# SIM_Socket.net
KiCad netlist of a schematic drawn in Altium Designer
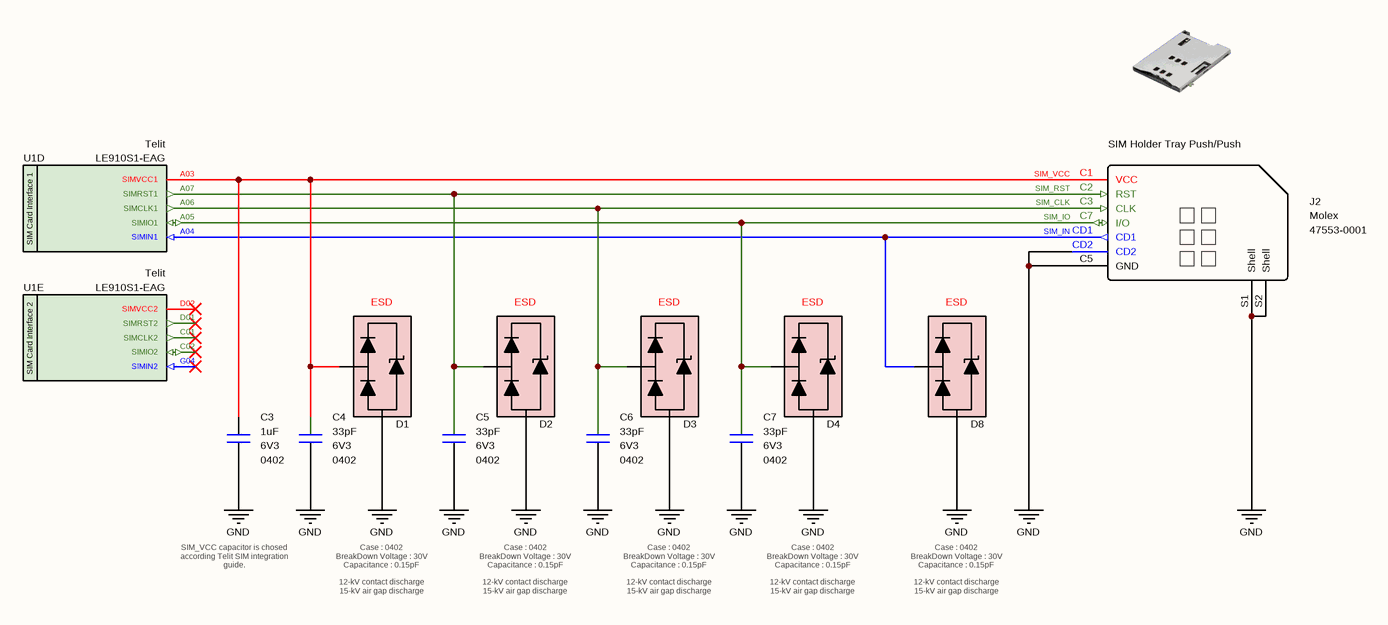
[diagram p0: SIM Socket.SchDoc]

(export (version "E")
  (design (tool "Eeschema 10.0.6"))
  (components
    (comp (ref "C3")
      (value "1uF")
      (footprint "Capacitor 0402")
      (description "Multilayer Ceramic Capacitors - SMD - 6.3V 1uF X5R 0402 20%")
      (fields
        (field (name "MANUFACTURER PART NUMBER") "GRM153R60J105ME95D")
        (field (name "TOLERANCE") "20%")
        (field (name "CASE") "0402")
        (field (name "VOLTAGE") "6V3")
      )
      (libsource (lib "P101DA_Library") (part "1uF [0402-6V3]"))
    )
    (comp (ref "C4")
      (value "33pF")
      (footprint "CAPACITOR_0402")
      (description "Capacitor - 33pF [0402] (Ceramic)")
      (fields
        (field (name "CASE") "0402")
        (field (name "VOLTAGE") "6V3")
        (field (name "MANUFACTURER PART NUMBER") "C0402C330J9RACAUTO")
        (field (name "TOLERANCE") "10%")
      )
      (libsource (lib "P101DA_Library") (part "33pF [0402-6V3]"))
    )
    (comp (ref "C5")
      (value "33pF")
      (footprint "CAPACITOR_0402")
      (description "Capacitor - 33pF [0402] (Ceramic)")
      (fields
        (field (name "CASE") "0402")
        (field (name "VOLTAGE") "6V3")
        (field (name "MANUFACTURER PART NUMBER") "C0402C330J9RACAUTO")
        (field (name "TOLERANCE") "10%")
      )
      (libsource (lib "P101DA_Library") (part "33pF [0402-6V3]"))
    )
    (comp (ref "C6")
      (value "33pF")
      (footprint "CAPACITOR_0402")
      (description "Capacitor - 33pF [0402] (Ceramic)")
      (fields
        (field (name "CASE") "0402")
        (field (name "VOLTAGE") "6V3")
        (field (name "MANUFACTURER PART NUMBER") "C0402C330J9RACAUTO")
        (field (name "TOLERANCE") "10%")
      )
      (libsource (lib "P101DA_Library") (part "33pF [0402-6V3]"))
    )
    (comp (ref "C7")
      (value "33pF")
      (footprint "CAPACITOR_0402")
      (description "Capacitor - 33pF [0402] (Ceramic)")
      (fields
        (field (name "CASE") "0402")
        (field (name "VOLTAGE") "6V3")
        (field (name "MANUFACTURER PART NUMBER") "C0402C330J9RACAUTO")
        (field (name "TOLERANCE") "10%")
      )
      (libsource (lib "P101DA_Library") (part "33pF [0402-6V3]"))
    )
    (comp (ref "D1")
      (value "0402ESDA-MLP1")
      (footprint "ESD_0402")
      (description "SUPPRESSOR ESD 30VDC 0402 HFREE")
      (libsource (lib "P101DA_Library") (part "Diode - TPD1E05U06DPYR"))
    )
    (comp (ref "D2")
      (value "0402ESDA-MLP1")
      (footprint "ESD_0402")
      (description "SUPPRESSOR ESD 30VDC 0402 HFREE")
      (libsource (lib "P101DA_Library") (part "Diode - TPD1E05U06DPYR"))
    )
    (comp (ref "D3")
      (value "0402ESDA-MLP1")
      (footprint "ESD_0402")
      (description "SUPPRESSOR ESD 30VDC 0402 HFREE")
      (libsource (lib "P101DA_Library") (part "Diode - TPD1E05U06DPYR"))
    )
    (comp (ref "D4")
      (value "0402ESDA-MLP1")
      (footprint "ESD_0402")
      (description "SUPPRESSOR ESD 30VDC 0402 HFREE")
      (libsource (lib "P101DA_Library") (part "Diode - TPD1E05U06DPYR"))
    )
    (comp (ref "D8")
      (value "0402ESDA-MLP1")
      (footprint "ESD_0402")
      (description "SUPPRESSOR ESD 30VDC 0402 HFREE")
      (libsource (lib "P101DA_Library") (part "Diode - TPD1E05U06DPYR"))
    )
    (comp (ref "J2")
      (value "~")
      (footprint "Connector - SIM Tray")
      (description "Memory Card Connectors ASSY 1.90 SIM CARD R IM CARD READER CONN.")
      (fields
        (field (name "CARD TYPE") "SIM Holder Tray Push/Push")
        (field (name "MANUFACTURER NAME") "Molex")
        (field (name "MANUFACTURER PART NUMBER") "47553-0001")
      )
      (libsource (lib "P101DA_Library") (part "Sim Holder"))
    )
    (comp (ref "U1")
      (value "LE910S1-EAG LTE GSM Module")
      (footprint "LE910 GSM Modem")
      (description "Telit LE910S1-EAG GPRS/GNSS Module")
      (fields
        (field (name "MANUFACTURER PART NUMBER") "LE910S1-EAG")
        (field (name "MANUFACTURER NAME") "Telit")
      )
      (libsource (lib "P101DA_Library") (part "IC - LE910S1-EAG"))
    )
  )
  (nets
    (net (code "1") (name "/SIM_CLK") (class "Default")
      (node (ref "C6") (pin "2") (pinfunction "2_2") (pintype "passive"))
      (node (ref "D3") (pin "1") (pinfunction "I/O_1") (pintype "passive"))
      (node (ref "J2") (pin "C3") (pinfunction "CLK_C3") (pintype "input"))
      (node (ref "U1") (pin "A06") (pinfunction "SIMCLK1_A06") (pintype "output"))
    )
    (net (code "2") (name "/SIM_IN") (class "Default")
      (node (ref "D8") (pin "1") (pinfunction "I/O_1") (pintype "passive"))
      (node (ref "J2") (pin "CD1") (pinfunction "CD1_CD1") (pintype "output"))
      (node (ref "U1") (pin "A04") (pinfunction "SIMIN1_A04") (pintype "input"))
    )
    (net (code "3") (name "/SIM_IO") (class "Default")
      (node (ref "C7") (pin "2") (pinfunction "2_2") (pintype "passive"))
      (node (ref "D4") (pin "1") (pinfunction "I/O_1") (pintype "passive"))
      (node (ref "J2") (pin "C7") (pinfunction "I/O_C7") (pintype "bidirectional"))
      (node (ref "U1") (pin "A05") (pinfunction "SIMIO1_A05") (pintype "bidirectional"))
    )
    (net (code "4") (name "/SIM_RST") (class "Default")
      (node (ref "C5") (pin "2") (pinfunction "2_2") (pintype "passive"))
      (node (ref "D2") (pin "1") (pinfunction "I/O_1") (pintype "passive"))
      (node (ref "J2") (pin "C2") (pinfunction "RST_C2") (pintype "input"))
      (node (ref "U1") (pin "A07") (pinfunction "SIMRST1_A07") (pintype "output"))
    )
    (net (code "5") (name "/SIM_VCC") (class "Default")
      (node (ref "C3") (pin "2") (pinfunction "2_2") (pintype "passive"))
      (node (ref "C4") (pin "2") (pinfunction "2_2") (pintype "passive"))
      (node (ref "D1") (pin "1") (pinfunction "I/O_1") (pintype "passive"))
      (node (ref "J2") (pin "C1") (pinfunction "VCC_C1") (pintype "power_in"))
      (node (ref "U1") (pin "A03") (pinfunction "SIMVCC1_A03") (pintype "power_in"))
    )
    (net (code "6") (name "GND") (class "Default")
      (node (ref "C3") (pin "1") (pinfunction "1_1") (pintype "passive"))
      (node (ref "C4") (pin "1") (pinfunction "1_1") (pintype "passive"))
      (node (ref "C5") (pin "1") (pinfunction "1_1") (pintype "passive"))
      (node (ref "C6") (pin "1") (pinfunction "1_1") (pintype "passive"))
      (node (ref "C7") (pin "1") (pinfunction "1_1") (pintype "passive"))
      (node (ref "D1") (pin "2") (pinfunction "GND_2") (pintype "passive"))
      (node (ref "D2") (pin "2") (pinfunction "GND_2") (pintype "passive"))
      (node (ref "D3") (pin "2") (pinfunction "GND_2") (pintype "passive"))
      (node (ref "D4") (pin "2") (pinfunction "GND_2") (pintype "passive"))
      (node (ref "D8") (pin "2") (pinfunction "GND_2") (pintype "passive"))
      (node (ref "J2") (pin "C5") (pinfunction "GND_C5") (pintype "power_in"))
      (node (ref "J2") (pin "CD2") (pinfunction "CD2_CD2") (pintype "passive"))
      (node (ref "J2") (pin "S1") (pinfunction "Shell_S1") (pintype "power_in"))
      (node (ref "J2") (pin "S2") (pinfunction "Shell_S2") (pintype "power_in"))
    )
    (net (code "7") (name "unconnected-(U1E-SIMCLK2-PadC01)") (class "Default")
      (node (ref "U1") (pin "C01") (pinfunction "SIMCLK2_C01") (pintype "output+no_connect"))
    )
    (net (code "8") (name "unconnected-(U1E-SIMIN2-PadG04)") (class "Default")
      (node (ref "U1") (pin "G04") (pinfunction "SIMIN2_G04") (pintype "input+no_connect"))
    )
    (net (code "9") (name "unconnected-(U1E-SIMIO2-PadC02)") (class "Default")
      (node (ref "U1") (pin "C02") (pinfunction "SIMIO2_C02") (pintype "bidirectional+no_connect"))
    )
    (net (code "10") (name "unconnected-(U1E-SIMRST2-PadD01)") (class "Default")
      (node (ref "U1") (pin "D01") (pinfunction "SIMRST2_D01") (pintype "output+no_connect"))
    )
    (net (code "11") (name "unconnected-(U1E-SIMVCC2-PadD02)") (class "Default")
      (node (ref "U1") (pin "D02") (pinfunction "SIMVCC2_D02") (pintype "passive+no_connect"))
    )
  )
)
